# Speedy_V2.net
KiCad netlist of a schematic drawn in EAGLE
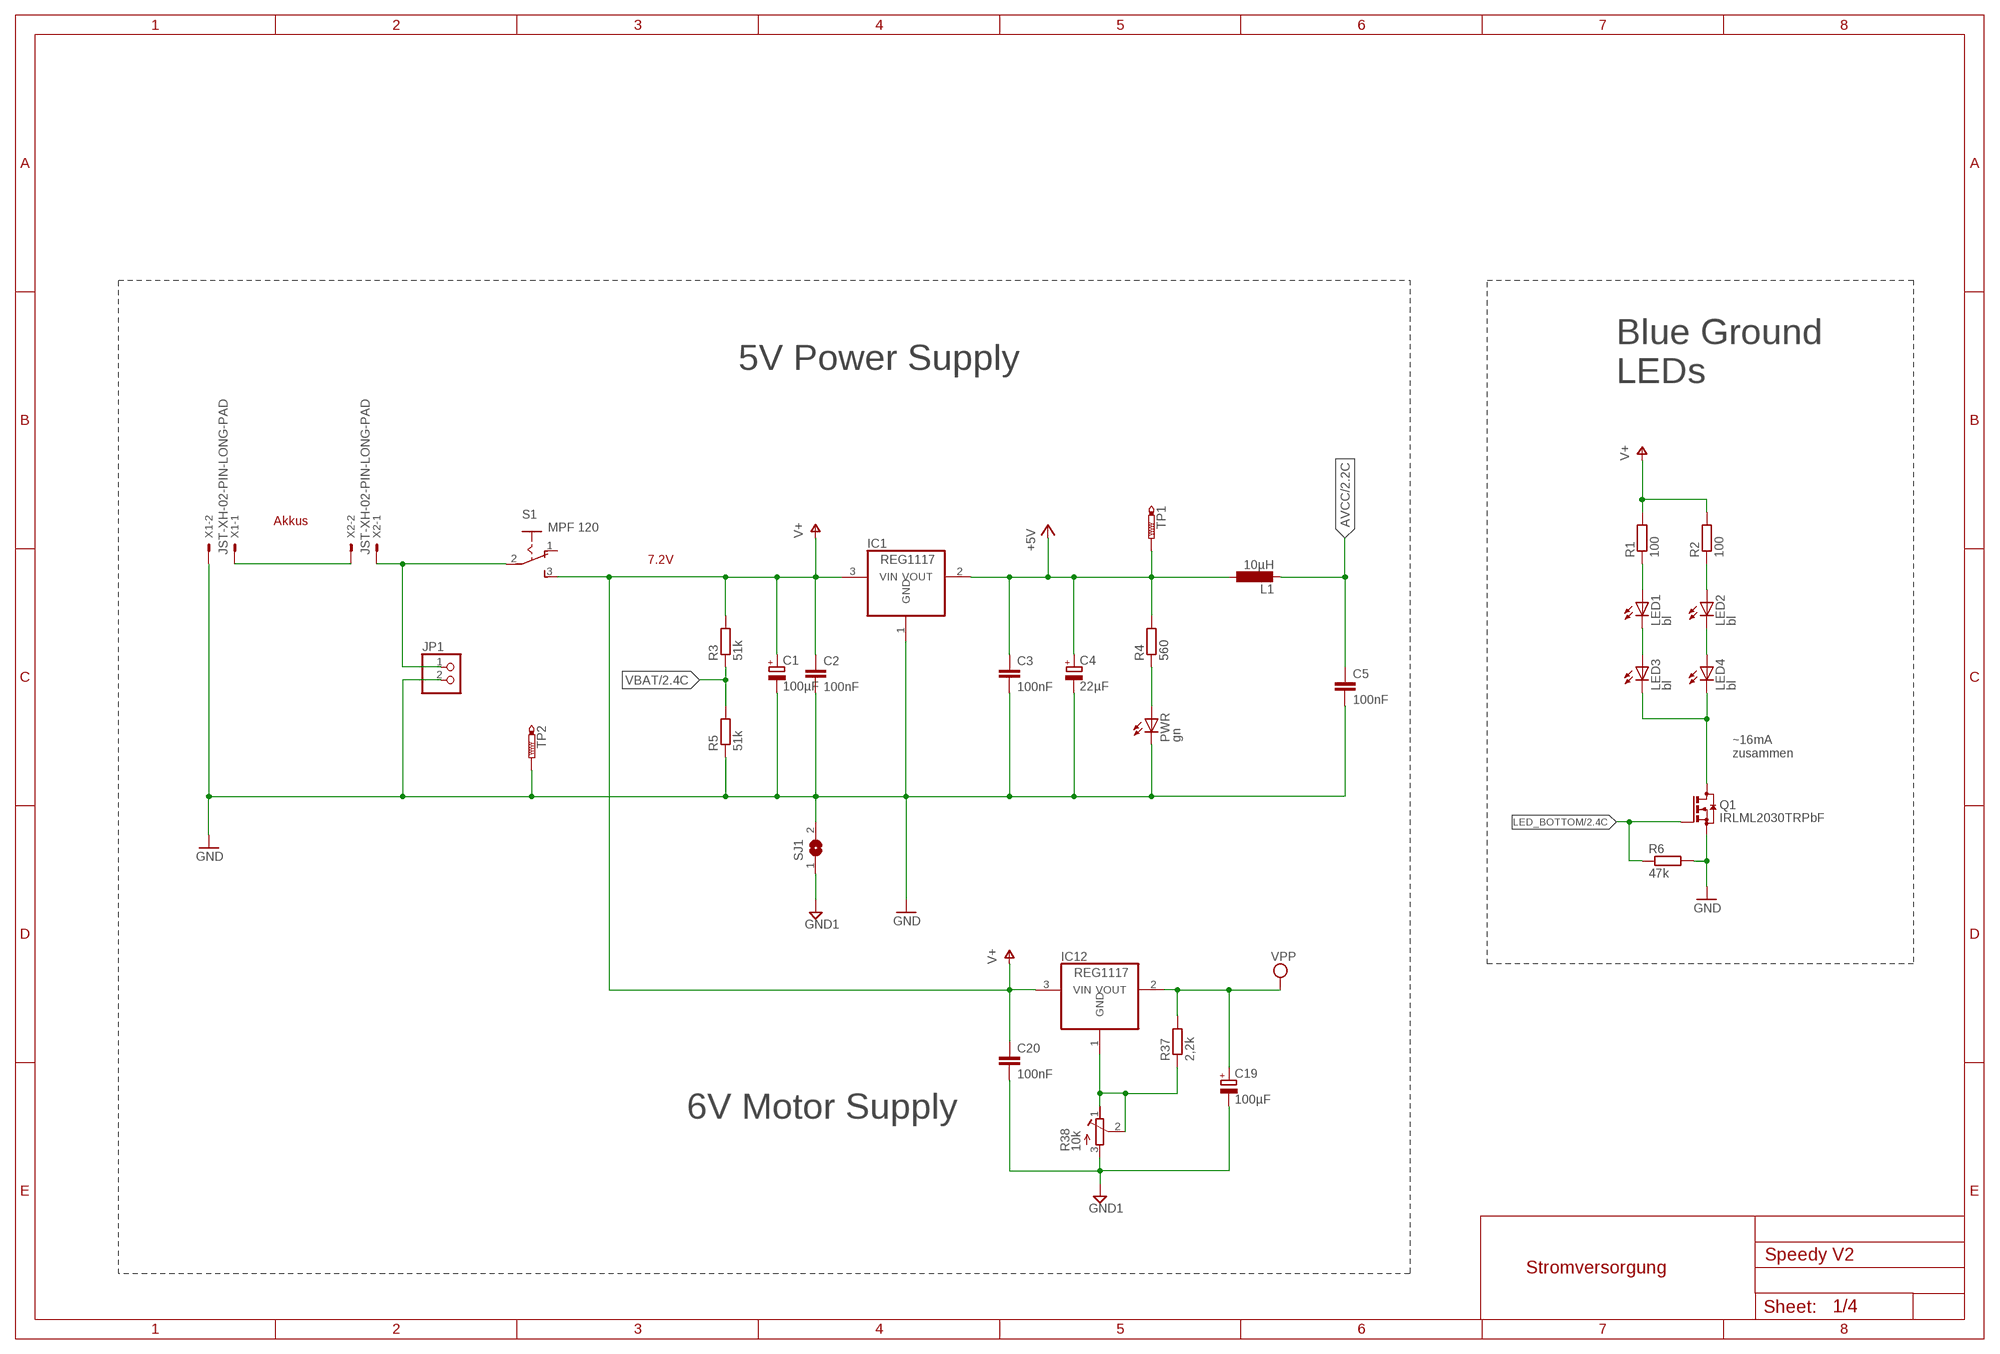
[diagram p0: schematic, sheet 1]
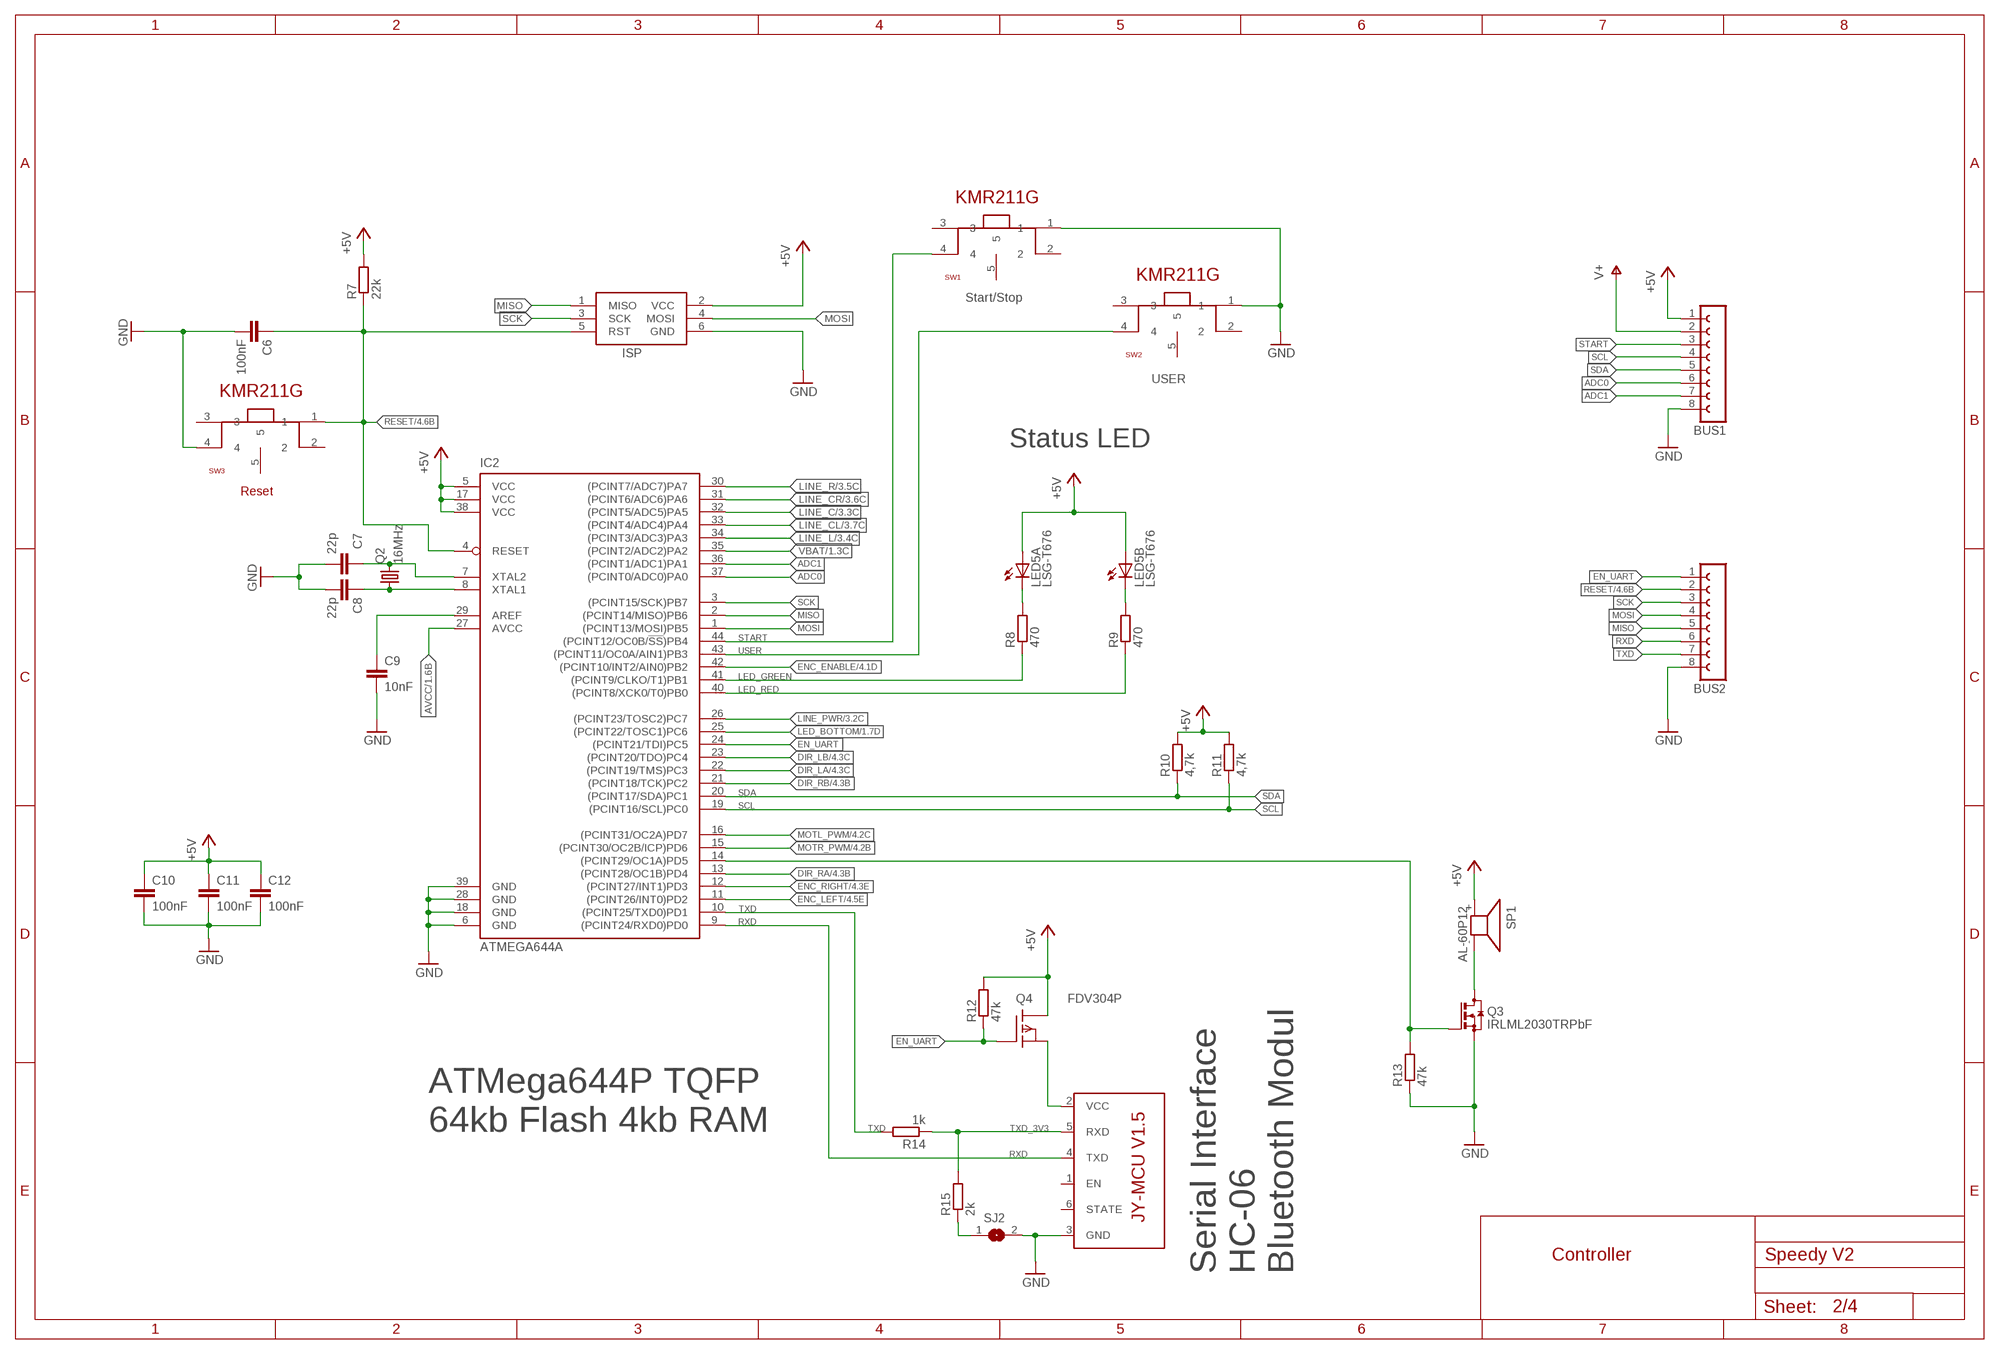
[diagram p1: schematic, sheet 2]
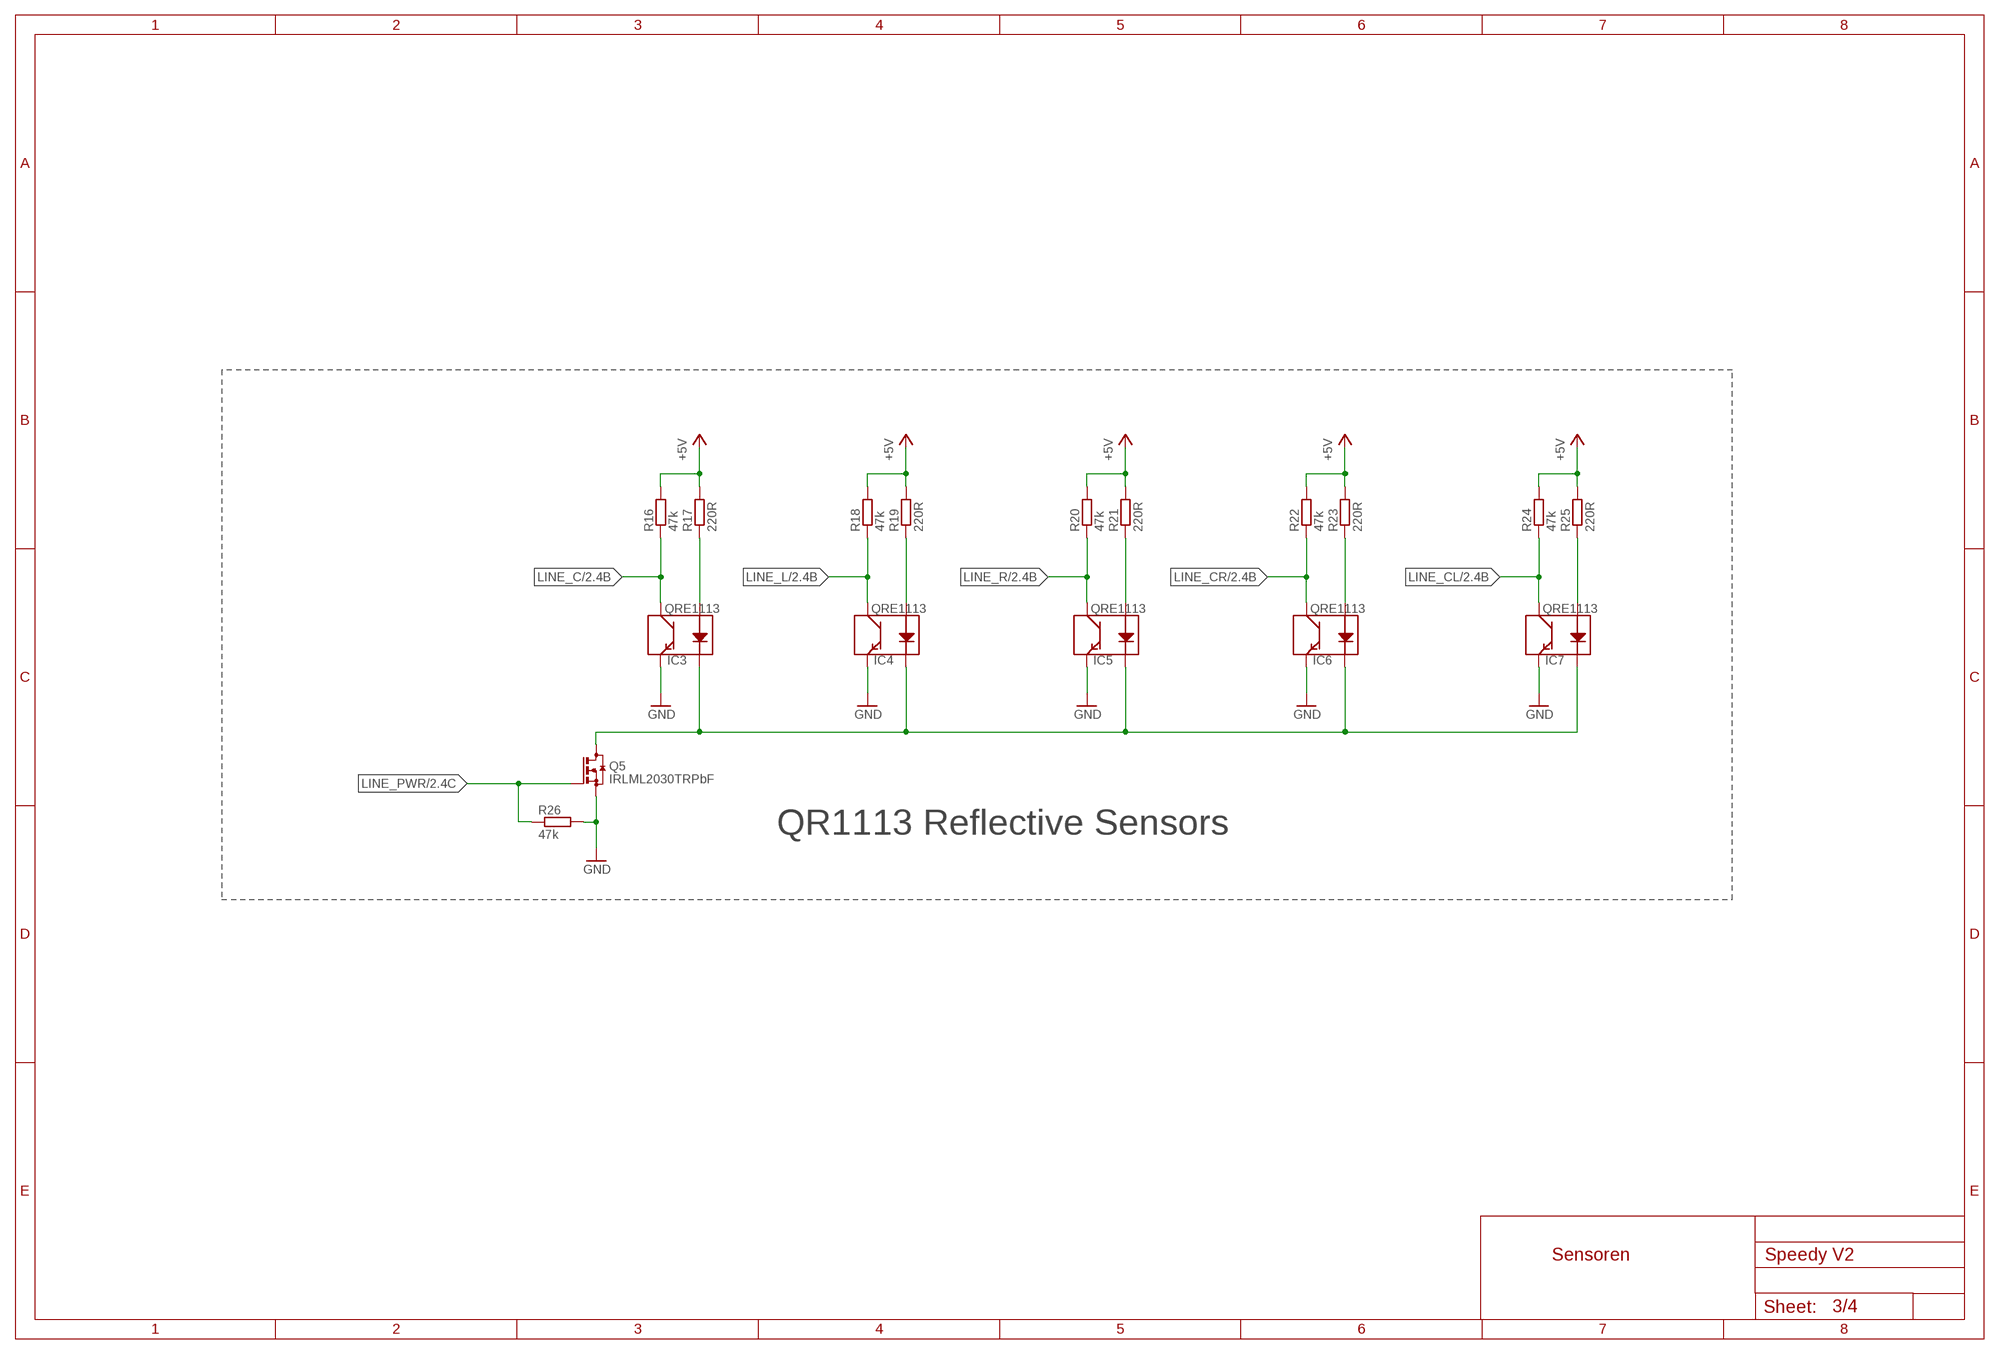
[diagram p2: schematic, sheet 3]
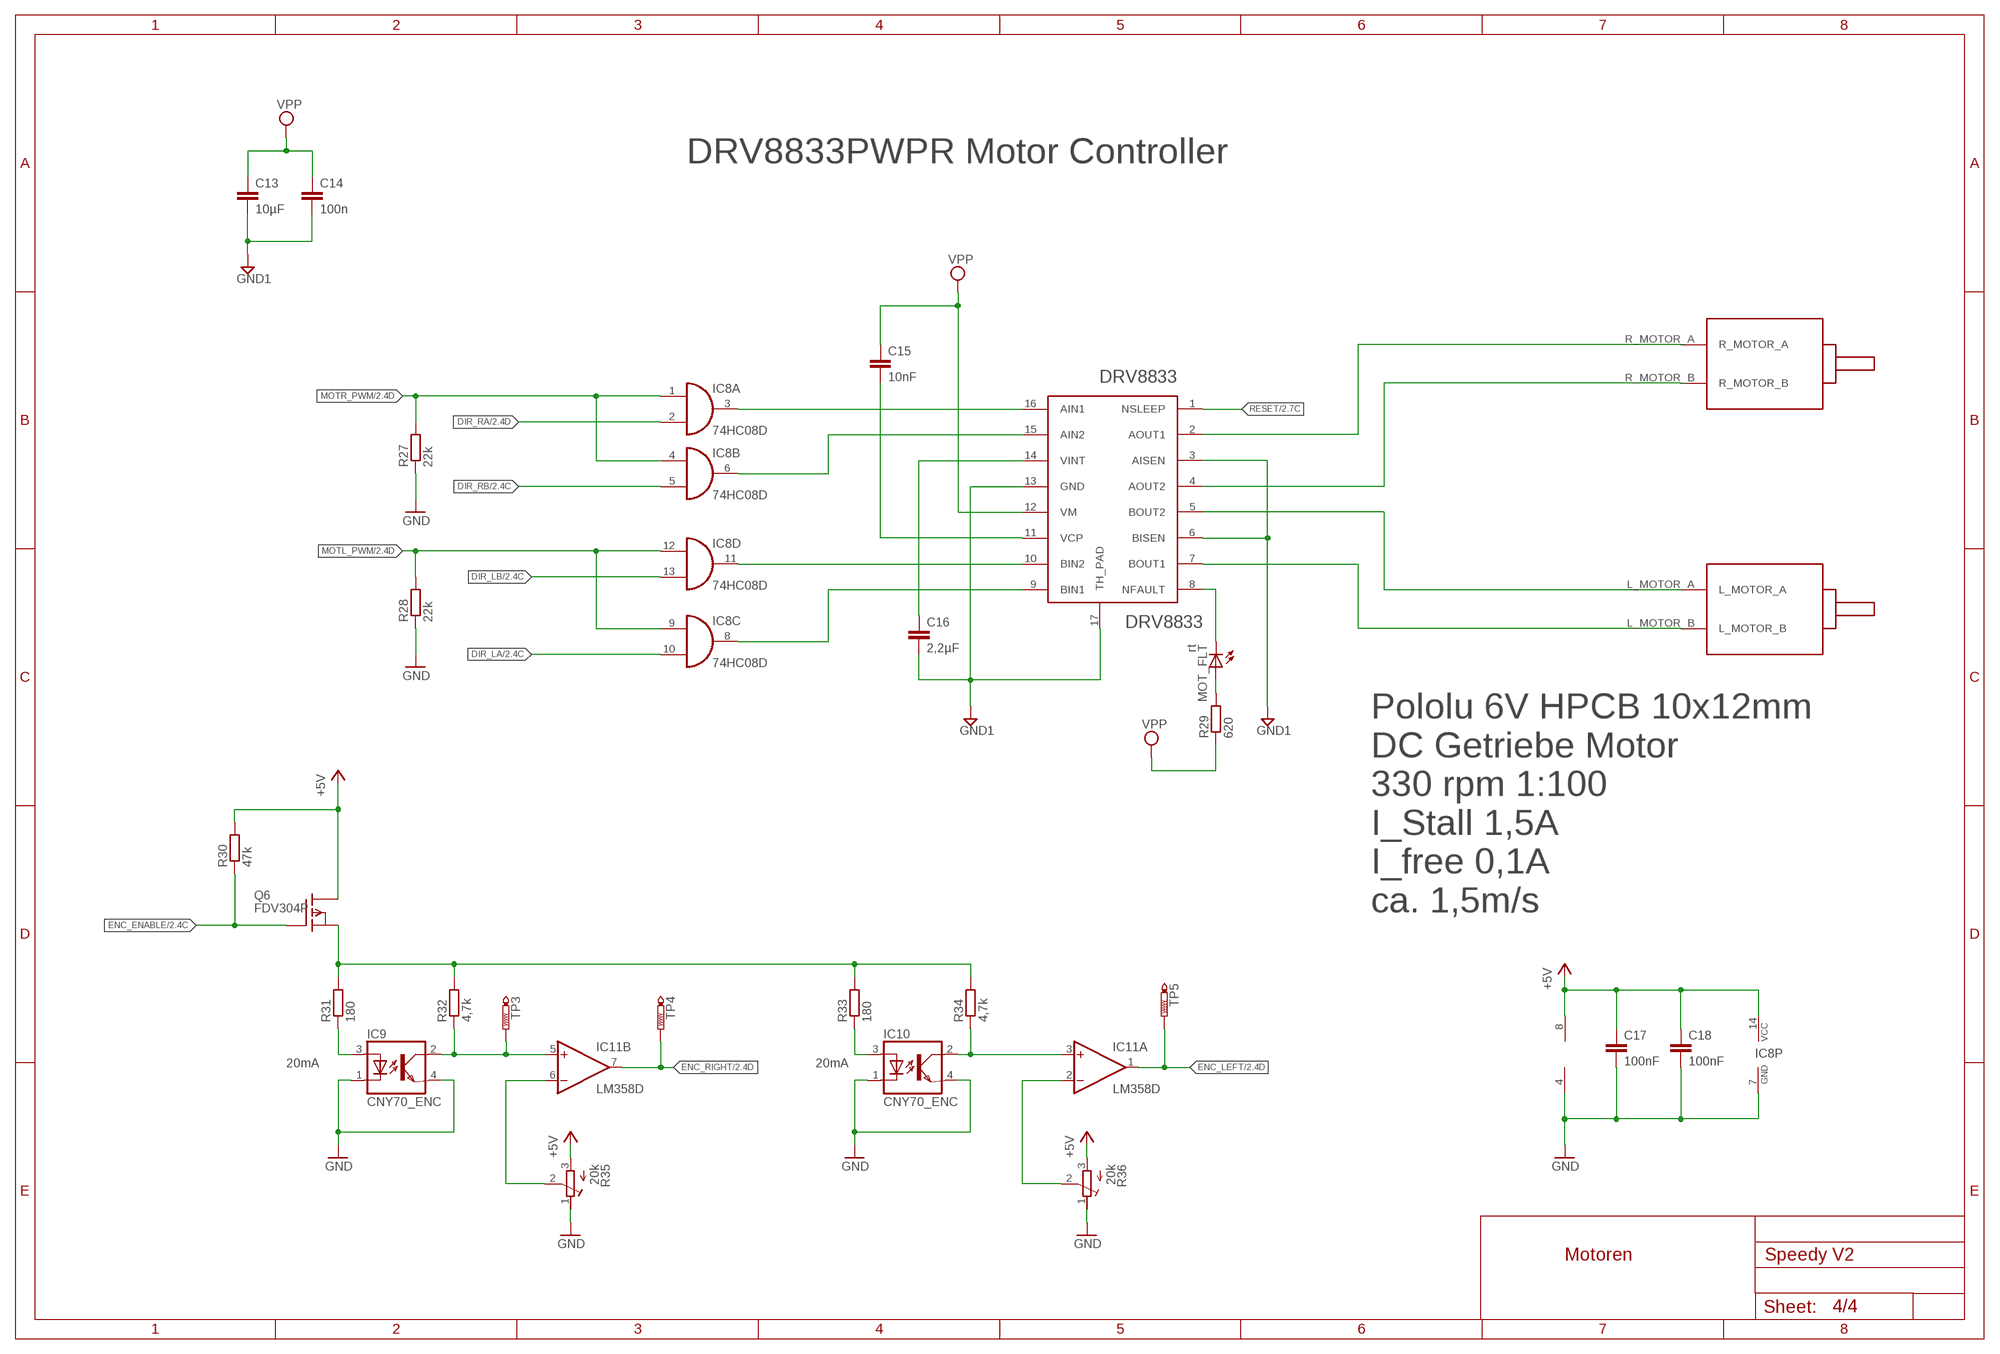
[diagram p3: schematic, sheet 4]

(export (version "E")
  (design (tool "Eeschema 10.0.6"))
  (components
    (comp (ref "IC3")
      (value "QRE1113")
      (footprint "eagle-import:QRE1113")
      (libsource (lib "eagle-import") (part "QRE1113"))
    )
    (comp (ref "IC4")
      (value "QRE1113")
      (footprint "eagle-import:QRE1113")
      (libsource (lib "eagle-import") (part "QRE1113"))
    )
    (comp (ref "IC5")
      (value "QRE1113")
      (footprint "eagle-import:QRE1113")
      (libsource (lib "eagle-import") (part "QRE1113"))
    )
    (comp (ref "IC6")
      (value "QRE1113")
      (footprint "eagle-import:QRE1113")
      (libsource (lib "eagle-import") (part "QRE1113"))
    )
    (comp (ref "IC7")
      (value "QRE1113")
      (footprint "eagle-import:QRE1113")
      (libsource (lib "eagle-import") (part "QRE1113"))
    )
    (comp (ref "Q5")
      (value "IRLML2030TRPbF")
      (footprint "eagle-import:SOT23")
      (libsource (lib "eagle-import") (part "BSS123"))
    )
    (comp (ref "R16")
      (value "47k")
      (footprint "eagle-import:R0805")
      (libsource (lib "eagle-import") (part "R-EU_R0805"))
    )
    (comp (ref "R17")
      (value "220R")
      (footprint "eagle-import:R0805")
      (libsource (lib "eagle-import") (part "R-EU_R0805"))
    )
    (comp (ref "R18")
      (value "47k")
      (footprint "eagle-import:R0805")
      (libsource (lib "eagle-import") (part "R-EU_R0805"))
    )
    (comp (ref "R19")
      (value "220R")
      (footprint "eagle-import:R0805")
      (libsource (lib "eagle-import") (part "R-EU_R0805"))
    )
    (comp (ref "R20")
      (value "47k")
      (footprint "eagle-import:R0805")
      (libsource (lib "eagle-import") (part "R-EU_R0805"))
    )
    (comp (ref "R21")
      (value "220R")
      (footprint "eagle-import:R0805")
      (libsource (lib "eagle-import") (part "R-EU_R0805"))
    )
    (comp (ref "R22")
      (value "47k")
      (footprint "eagle-import:R0805")
      (libsource (lib "eagle-import") (part "R-EU_R0805"))
    )
    (comp (ref "R23")
      (value "220R")
      (footprint "eagle-import:R0805")
      (libsource (lib "eagle-import") (part "R-EU_R0805"))
    )
    (comp (ref "R24")
      (value "47k")
      (footprint "eagle-import:R0805")
      (libsource (lib "eagle-import") (part "R-EU_R0805"))
    )
    (comp (ref "R25")
      (value "220R")
      (footprint "eagle-import:R0805")
      (libsource (lib "eagle-import") (part "R-EU_R0805"))
    )
    (comp (ref "R26")
      (value "47k")
      (footprint "eagle-import:R0805")
      (libsource (lib "eagle-import") (part "R-EU_R0805"))
    )
    (comp (ref "C13")
      (value "10µF")
      (footprint "eagle-import:C1206")
      (libsource (lib "eagle-import") (part "C-EUC1206"))
    )
    (comp (ref "C14")
      (value "100n")
      (footprint "eagle-import:C0805")
      (libsource (lib "eagle-import") (part "C-EUC0805"))
    )
    (comp (ref "C15")
      (value "10nF")
      (footprint "eagle-import:C0805")
      (libsource (lib "eagle-import") (part "C-EUC0805"))
    )
    (comp (ref "C16")
      (value "2,2µF")
      (footprint "eagle-import:C1206")
      (libsource (lib "eagle-import") (part "C-EUC1206"))
    )
    (comp (ref "C17")
      (value "100nF")
      (footprint "eagle-import:C0805")
      (libsource (lib "eagle-import") (part "C-EUC0805"))
    )
    (comp (ref "C18")
      (value "100nF")
      (footprint "eagle-import:C0805")
      (libsource (lib "eagle-import") (part "C-EUC0805"))
    )
    (comp (ref "IC8")
      (value "74HC08D")
      (footprint "eagle-import:SO14")
      (libsource (lib "eagle-import") (part "7408DHC"))
    )
    (comp (ref "IC9")
      (value "CNY70_ENC")
      (footprint "eagle-import:CNY70_ENC")
      (libsource (lib "eagle-import") (part "CNY70_ENC"))
    )
    (comp (ref "IC10")
      (value "CNY70_ENC")
      (footprint "eagle-import:CNY70_ENC")
      (libsource (lib "eagle-import") (part "CNY70_ENC"))
    )
    (comp (ref "IC11")
      (value "LM358D")
      (footprint "eagle-import:SO08")
      (libsource (lib "eagle-import") (part "LM358D"))
    )
    (comp (ref "MOT_FLT")
      (value "rt")
      (footprint "eagle-import:CHIP-LED0805")
      (libsource (lib "eagle-import") (part "LEDCHIP-LED0805"))
    )
    (comp (ref "Q6")
      (value "FDV304P")
      (footprint "eagle-import:SOT23")
      (libsource (lib "eagle-import") (part "FDV304P"))
    )
    (comp (ref "R27")
      (value "22k")
      (footprint "eagle-import:R0805")
      (libsource (lib "eagle-import") (part "R-EU_R0805"))
    )
    (comp (ref "R28")
      (value "22k")
      (footprint "eagle-import:R0805")
      (libsource (lib "eagle-import") (part "R-EU_R0805"))
    )
    (comp (ref "R29")
      (value "620")
      (footprint "eagle-import:R0805")
      (libsource (lib "eagle-import") (part "R-EU_R0805"))
    )
    (comp (ref "R30")
      (value "47k")
      (footprint "eagle-import:R0805")
      (libsource (lib "eagle-import") (part "R-EU_R0805"))
    )
    (comp (ref "R31")
      (value "180")
      (footprint "eagle-import:R0805")
      (libsource (lib "eagle-import") (part "R-EU_R0805"))
    )
    (comp (ref "R32")
      (value "4,7k")
      (footprint "eagle-import:R0805")
      (libsource (lib "eagle-import") (part "R-EU_R0805"))
    )
    (comp (ref "R33")
      (value "180")
      (footprint "eagle-import:R0805")
      (libsource (lib "eagle-import") (part "R-EU_R0805"))
    )
    (comp (ref "R34")
      (value "4,7k")
      (footprint "eagle-import:R0805")
      (libsource (lib "eagle-import") (part "R-EU_R0805"))
    )
    (comp (ref "R35")
      (value "20k")
      (footprint "eagle-import:RTRIM3314G")
      (libsource (lib "eagle-import") (part "R-TRIMM3314G"))
    )
    (comp (ref "R36")
      (value "20k")
      (footprint "eagle-import:RTRIM3314G")
      (libsource (lib "eagle-import") (part "R-TRIMM3314G"))
    )
    (comp (ref "TP3")
      (value "PTR1B1,27")
      (footprint "eagle-import:B1,27")
      (libsource (lib "eagle-import") (part "PTR1B1,27"))
    )
    (comp (ref "TP4")
      (value "PTR1B1,27")
      (footprint "eagle-import:B1,27")
      (libsource (lib "eagle-import") (part "PTR1B1,27"))
    )
    (comp (ref "TP5")
      (value "PTR1B1,27")
      (footprint "eagle-import:B1,27")
      (libsource (lib "eagle-import") (part "PTR1B1,27"))
    )
    (comp (ref "U2")
      (value "FUTURA_V1.0_MOTOR_MOUNT")
      (footprint "eagle-import:FUTURA_V1.0_MOTOT_MOUNT")
      (libsource (lib "eagle-import") (part "FUTURA_V1.0_MOTOR_MOUNT"))
    )
    (comp (ref "U3")
      (value "DRV8833")
      (footprint "eagle-import:SOP65P640X120-17N")
      (libsource (lib "eagle-import") (part "DRV8833"))
    )
    (comp (ref "C1")
      (value "100µF")
      (footprint "eagle-import:PANASONIC_D")
      (libsource (lib "eagle-import") (part "CPOL-EUD"))
    )
    (comp (ref "C2")
      (value "100nF")
      (footprint "eagle-import:C0805")
      (libsource (lib "eagle-import") (part "C-EUC0805"))
    )
    (comp (ref "C3")
      (value "100nF")
      (footprint "eagle-import:C0805")
      (libsource (lib "eagle-import") (part "C-EUC0805"))
    )
    (comp (ref "C4")
      (value "22µF")
      (footprint "eagle-import:PANASONIC_B")
      (libsource (lib "eagle-import") (part "CPOL-EUB"))
    )
    (comp (ref "C5")
      (value "100nF")
      (footprint "eagle-import:C0805")
      (libsource (lib "eagle-import") (part "C-EUC0805"))
    )
    (comp (ref "C19")
      (value "100µF")
      (footprint "eagle-import:PANASONIC_D")
      (libsource (lib "eagle-import") (part "CPOL-EUD"))
    )
    (comp (ref "C20")
      (value "100nF")
      (footprint "eagle-import:C0805")
      (libsource (lib "eagle-import") (part "C-EUC0805"))
    )
    (comp (ref "IC1")
      (value "REG1117")
      (footprint "eagle-import:SOT223")
      (libsource (lib "eagle-import") (part "REG1117"))
    )
    (comp (ref "IC12")
      (value "REG1117")
      (footprint "eagle-import:SOT223")
      (libsource (lib "eagle-import") (part "REG1117"))
    )
    (comp (ref "JP1")
      (value "PINHD-1X2")
      (footprint "eagle-import:1X02")
      (libsource (lib "eagle-import") (part "PINHD-1X2"))
    )
    (comp (ref "L1")
      (value "10µH")
      (footprint "eagle-import:C1210K")
      (libsource (lib "eagle-import") (part "L-1210"))
    )
    (comp (ref "LED1")
      (value "bl")
      (footprint "eagle-import:CHIPLED_0805")
      (libsource (lib "eagle-import") (part "LEDCHIPLED_0805"))
    )
    (comp (ref "LED2")
      (value "bl")
      (footprint "eagle-import:CHIPLED_0805")
      (libsource (lib "eagle-import") (part "LEDCHIPLED_0805"))
    )
    (comp (ref "LED3")
      (value "bl")
      (footprint "eagle-import:CHIPLED_0805")
      (libsource (lib "eagle-import") (part "LEDCHIPLED_0805"))
    )
    (comp (ref "LED4")
      (value "bl")
      (footprint "eagle-import:CHIPLED_0805")
      (libsource (lib "eagle-import") (part "LEDCHIPLED_0805"))
    )
    (comp (ref "PWR")
      (value "gn")
      (footprint "eagle-import:CHIPLED_0805")
      (libsource (lib "eagle-import") (part "LEDCHIPLED_0805"))
    )
    (comp (ref "Q1")
      (value "IRLML2030TRPbF")
      (footprint "eagle-import:SOT23")
      (libsource (lib "eagle-import") (part "BSS123"))
    )
    (comp (ref "R1")
      (value "100")
      (footprint "eagle-import:R0805")
      (libsource (lib "eagle-import") (part "R-EU_R0805"))
    )
    (comp (ref "R2")
      (value "100")
      (footprint "eagle-import:R0805")
      (libsource (lib "eagle-import") (part "R-EU_R0805"))
    )
    (comp (ref "R3")
      (value "51k")
      (footprint "eagle-import:R0805")
      (libsource (lib "eagle-import") (part "R-EU_R0805"))
    )
    (comp (ref "R4")
      (value "560")
      (footprint "eagle-import:R0805")
      (libsource (lib "eagle-import") (part "R-EU_R0805"))
    )
    (comp (ref "R5")
      (value "51k")
      (footprint "eagle-import:R0805")
      (libsource (lib "eagle-import") (part "R-EU_R0805"))
    )
    (comp (ref "R6")
      (value "47k")
      (footprint "eagle-import:R0805")
      (libsource (lib "eagle-import") (part "R-EU_R0805"))
    )
    (comp (ref "R37")
      (value "2,2k")
      (footprint "eagle-import:R0805")
      (libsource (lib "eagle-import") (part "R-EU_R0805"))
    )
    (comp (ref "R38")
      (value "10k")
      (footprint "eagle-import:RTRIM3314G")
      (libsource (lib "eagle-import") (part "R-TRIMM3314G"))
    )
    (comp (ref "S1")
      (value "MPF 120")
      (footprint "eagle-import:255SB")
      (libsource (lib "eagle-import") (part "255SB"))
    )
    (comp (ref "SJ1") (value "SJ") (footprint "eagle-import:SJ") (libsource (lib "eagle-import") (part "SJ")))
    (comp (ref "TP1")
      (value "PTR1B1,27")
      (footprint "eagle-import:B1,27")
      (libsource (lib "eagle-import") (part "PTR1B1,27"))
    )
    (comp (ref "TP2")
      (value "PTR1PAD1-13")
      (footprint "eagle-import:P1-13")
      (libsource (lib "eagle-import") (part "PTR1PAD1-13"))
    )
    (comp (ref "X1")
      (value "JST-XH-02-PIN-LONG-PAD")
      (footprint "eagle-import:JST-XH-02-PACKAGE-LONG-PAD")
      (libsource (lib "eagle-import") (part "JST-XH-02-PIN-LONG-PAD"))
    )
    (comp (ref "X2")
      (value "JST-XH-02-PIN-LONG-PAD")
      (footprint "eagle-import:JST-XH-02-PACKAGE-LONG-PAD")
      (libsource (lib "eagle-import") (part "JST-XH-02-PIN-LONG-PAD"))
    )
    (comp (ref "BUS1")
      (value "FE08-1")
      (footprint "eagle-import:FE08")
      (libsource (lib "eagle-import") (part "FE08-1"))
    )
    (comp (ref "BUS2")
      (value "FE08-1")
      (footprint "eagle-import:FE08")
      (libsource (lib "eagle-import") (part "FE08-1"))
    )
    (comp (ref "C6")
      (value "100nF")
      (footprint "eagle-import:C0805")
      (libsource (lib "eagle-import") (part "C-EUC0805"))
    )
    (comp (ref "C7")
      (value "22p")
      (footprint "eagle-import:C0603")
      (libsource (lib "eagle-import") (part "C-EUC0603"))
    )
    (comp (ref "C8")
      (value "22p")
      (footprint "eagle-import:C0603")
      (libsource (lib "eagle-import") (part "C-EUC0603"))
    )
    (comp (ref "C9")
      (value "10nF")
      (footprint "eagle-import:C0603")
      (libsource (lib "eagle-import") (part "C-EUC0603"))
    )
    (comp (ref "C10")
      (value "100nF")
      (footprint "eagle-import:C0603")
      (libsource (lib "eagle-import") (part "C-EUC0603"))
    )
    (comp (ref "C11")
      (value "100nF")
      (footprint "eagle-import:C0603")
      (libsource (lib "eagle-import") (part "C-EUC0603"))
    )
    (comp (ref "C12")
      (value "100nF")
      (footprint "eagle-import:C0603")
      (libsource (lib "eagle-import") (part "C-EUC0603"))
    )
    (comp (ref "IC2")
      (value "ATMEGA644A")
      (footprint "eagle-import:TQFP44")
      (fields (field (name "MPN") "ATMEGA644PV-10AU"))
      (libsource (lib "eagle-import") (part "ATMEGA644A"))
    )
    (comp (ref "ISP")
      (value "AVRISP-6")
      (footprint "eagle-import:AVRISP")
      (libsource (lib "eagle-import") (part "AVRISP-6"))
    )
    (comp (ref "LED5")
      (value "LSG-T676")
      (footprint "eagle-import:P-LCC4-0")
      (libsource (lib "eagle-import") (part "LSG-T676"))
    )
    (comp (ref "Q2")
      (value "16MHz")
      (footprint "eagle-import:7X5MMQUARZ")
      (libsource (lib "eagle-import") (part "7X5MMMQ"))
    )
    (comp (ref "Q3")
      (value "IRLML2030TRPbF")
      (footprint "eagle-import:SOT23")
      (libsource (lib "eagle-import") (part "BSS123"))
    )
    (comp (ref "Q4")
      (value "FDV304P")
      (footprint "eagle-import:SOT23")
      (libsource (lib "eagle-import") (part "FDV304P"))
    )
    (comp (ref "R7")
      (value "22k")
      (footprint "eagle-import:R0805")
      (libsource (lib "eagle-import") (part "R-EU_R0805"))
    )
    (comp (ref "R8")
      (value "470")
      (footprint "eagle-import:R0805")
      (libsource (lib "eagle-import") (part "R-EU_R0805"))
    )
    (comp (ref "R9")
      (value "470")
      (footprint "eagle-import:R0805")
      (libsource (lib "eagle-import") (part "R-EU_R0805"))
    )
    (comp (ref "R10")
      (value "4,7k")
      (footprint "eagle-import:R0805")
      (libsource (lib "eagle-import") (part "R-EU_R0805"))
    )
    (comp (ref "R11")
      (value "4,7k")
      (footprint "eagle-import:R0805")
      (libsource (lib "eagle-import") (part "R-EU_R0805"))
    )
    (comp (ref "R12")
      (value "47k")
      (footprint "eagle-import:R0805")
      (libsource (lib "eagle-import") (part "R-EU_R0805"))
    )
    (comp (ref "R13")
      (value "47k")
      (footprint "eagle-import:R0805")
      (libsource (lib "eagle-import") (part "R-EU_R0805"))
    )
    (comp (ref "R14")
      (value "1k")
      (footprint "eagle-import:R0805")
      (libsource (lib "eagle-import") (part "R-EU_R0805"))
    )
    (comp (ref "R15")
      (value "2k")
      (footprint "eagle-import:R0805")
      (libsource (lib "eagle-import") (part "R-EU_R0805"))
    )
    (comp (ref "SJ2") (value "SJ") (footprint "eagle-import:SJ") (libsource (lib "eagle-import") (part "SJ")))
    (comp (ref "SP1")
      (value "AL-60P12")
      (footprint "eagle-import:KSS1201")
      (libsource (lib "eagle-import") (part "KSS1201"))
    )
    (comp (ref "SW1")
      (value "KMR211G_SWITCH")
      (footprint "eagle-import:KMR211G_SWITCH")
      (libsource (lib "eagle-import") (part "KMR211G_SWITCH"))
    )
    (comp (ref "SW2")
      (value "KMR211G_SWITCH")
      (footprint "eagle-import:KMR211G_SWITCH")
      (libsource (lib "eagle-import") (part "KMR211G_SWITCH"))
    )
    (comp (ref "SW3")
      (value "KMR211G_SWITCH")
      (footprint "eagle-import:KMR211G_SWITCH")
      (libsource (lib "eagle-import") (part "KMR211G_SWITCH"))
    )
    (comp (ref "U1")
      (value "BT_BOARD")
      (footprint "eagle-import:BT_BOARD")
      (libsource (lib "eagle-import") (part "BT_BOARD"))
    )
  )
  (nets
    (net (code "1") (name "+5V") (class "Default")
      (node (ref "BUS1") (pin "1") (pinfunction "1_1") (pintype "passive"))
      (node (ref "C10") (pin "1") (pinfunction "1_1") (pintype "passive"))
      (node (ref "C11") (pin "1") (pinfunction "1_1") (pintype "passive"))
      (node (ref "C12") (pin "1") (pinfunction "1_1") (pintype "passive"))
      (node (ref "C17") (pin "1") (pinfunction "1_1") (pintype "passive"))
      (node (ref "C18") (pin "1") (pinfunction "1_1") (pintype "passive"))
      (node (ref "C3") (pin "1") (pinfunction "1_1") (pintype "passive"))
      (node (ref "C4") (pin "+") (pinfunction "+_+") (pintype "passive"))
      (node (ref "IC1") (pin "2") (pinfunction "VOUT_2") (pintype "output"))
      (node (ref "IC11") (pin "8") (pinfunction "V+_8") (pintype "power_in"))
      (node (ref "IC2") (pin "17") (pinfunction "VCC_17") (pintype "power_in"))
      (node (ref "IC2") (pin "38") (pinfunction "VCC_38") (pintype "power_in"))
      (node (ref "IC2") (pin "5") (pinfunction "VCC_5") (pintype "power_in"))
      (node (ref "IC8") (pin "14") (pinfunction "VCC_14") (pintype "power_in"))
      (node (ref "ISP") (pin "2") (pinfunction "VCC_2") (pintype "power_in"))
      (node (ref "L1") (pin "1") (pinfunction "1_1") (pintype "passive"))
      (node (ref "LED5") (pin "2") (pinfunction "A_2") (pintype "passive"))
      (node (ref "LED5") (pin "4") (pinfunction "A_4") (pintype "passive"))
      (node (ref "Q4") (pin "D") (pinfunction "D_D") (pintype "passive"))
      (node (ref "Q6") (pin "D") (pinfunction "D_D") (pintype "passive"))
      (node (ref "R10") (pin "2") (pinfunction "2_2") (pintype "passive"))
      (node (ref "R11") (pin "2") (pinfunction "2_2") (pintype "passive"))
      (node (ref "R12") (pin "2") (pinfunction "2_2") (pintype "passive"))
      (node (ref "R16") (pin "2") (pinfunction "2_2") (pintype "passive"))
      (node (ref "R17") (pin "2") (pinfunction "2_2") (pintype "passive"))
      (node (ref "R18") (pin "2") (pinfunction "2_2") (pintype "passive"))
      (node (ref "R19") (pin "2") (pinfunction "2_2") (pintype "passive"))
      (node (ref "R20") (pin "2") (pinfunction "2_2") (pintype "passive"))
      (node (ref "R21") (pin "2") (pinfunction "2_2") (pintype "passive"))
      (node (ref "R22") (pin "2") (pinfunction "2_2") (pintype "passive"))
      (node (ref "R23") (pin "2") (pinfunction "2_2") (pintype "passive"))
      (node (ref "R24") (pin "2") (pinfunction "2_2") (pintype "passive"))
      (node (ref "R25") (pin "2") (pinfunction "2_2") (pintype "passive"))
      (node (ref "R30") (pin "2") (pinfunction "2_2") (pintype "passive"))
      (node (ref "R35") (pin "3") (pinfunction "A_3") (pintype "passive"))
      (node (ref "R36") (pin "3") (pinfunction "A_3") (pintype "passive"))
      (node (ref "R4") (pin "2") (pinfunction "2_2") (pintype "passive"))
      (node (ref "R7") (pin "2") (pinfunction "2_2") (pintype "passive"))
      (node (ref "SP1") (pin "+") (pinfunction "1_+") (pintype "passive"))
      (node (ref "TP1") (pin "TP") (pinfunction "TP_TP") (pintype "input"))
    )
    (net (code "2") (name "ADC0") (class "Default")
      (node (ref "BUS1") (pin "6") (pinfunction "6_6") (pintype "passive"))
      (node (ref "IC2") (pin "37") (pinfunction "(PCINT0/ADC0)PA0_37") (pintype "bidirectional"))
    )
    (net (code "3") (name "ADC1") (class "Default")
      (node (ref "BUS1") (pin "7") (pinfunction "7_7") (pintype "passive"))
      (node (ref "IC2") (pin "36") (pinfunction "(PCINT1/ADC1)PA1_36") (pintype "bidirectional"))
    )
    (net (code "4") (name "AVCC") (class "Default")
      (node (ref "C5") (pin "1") (pinfunction "1_1") (pintype "passive"))
      (node (ref "IC2") (pin "27") (pinfunction "AVCC_27") (pintype "power_in"))
      (node (ref "L1") (pin "2") (pinfunction "2_2") (pintype "passive"))
    )
    (net (code "5") (name "DIR_LA") (class "Default")
      (node (ref "IC2") (pin "22") (pinfunction "(PCINT19/TMS)PC3_22") (pintype "output"))
      (node (ref "IC8") (pin "10") (pinfunction "I1_10") (pintype "input"))
    )
    (net (code "6") (name "DIR_LB") (class "Default")
      (node (ref "IC2") (pin "23") (pinfunction "(PCINT20/TDO)PC4_23") (pintype "output"))
      (node (ref "IC8") (pin "13") (pinfunction "I1_13") (pintype "input"))
    )
    (net (code "7") (name "DIR_RA") (class "Default")
      (node (ref "IC2") (pin "13") (pinfunction "(PCINT28/OC1B)PD4_13") (pintype "bidirectional"))
      (node (ref "IC8") (pin "2") (pinfunction "I1_2") (pintype "input"))
    )
    (net (code "8") (name "DIR_RB") (class "Default")
      (node (ref "IC2") (pin "21") (pinfunction "(PCINT18/TCK)PC2_21") (pintype "output"))
      (node (ref "IC8") (pin "5") (pinfunction "I1_5") (pintype "input"))
    )
    (net (code "9") (name "ENC_ENABLE") (class "Default")
      (node (ref "IC2") (pin "42") (pinfunction "(PCINT10/INT2/AIN0)PB2_42") (pintype "bidirectional"))
      (node (ref "Q6") (pin "G") (pinfunction "G_G") (pintype "passive"))
      (node (ref "R30") (pin "1") (pinfunction "1_1") (pintype "passive"))
    )
    (net (code "10") (name "ENC_LEFT") (class "Default")
      (node (ref "IC11") (pin "1") (pinfunction "OUT_1") (pintype "output"))
      (node (ref "IC2") (pin "11") (pinfunction "(PCINT26/INT0)PD2_11") (pintype "bidirectional"))
      (node (ref "TP5") (pin "TP") (pinfunction "TP_TP") (pintype "input"))
    )
    (net (code "11") (name "ENC_RIGHT") (class "Default")
      (node (ref "IC11") (pin "7") (pinfunction "OUT_7") (pintype "output"))
      (node (ref "IC2") (pin "12") (pinfunction "(PCINT27/INT1)PD3_12") (pintype "bidirectional"))
      (node (ref "TP4") (pin "TP") (pinfunction "TP_TP") (pintype "input"))
    )
    (net (code "12") (name "EN_UART") (class "Default")
      (node (ref "BUS2") (pin "1") (pinfunction "1_1") (pintype "passive"))
      (node (ref "IC2") (pin "24") (pinfunction "(PCINT21/TDI)PC5_24") (pintype "output"))
      (node (ref "Q4") (pin "G") (pinfunction "G_G") (pintype "passive"))
      (node (ref "R12") (pin "1") (pinfunction "1_1") (pintype "passive"))
    )
    (net (code "13") (name "GND") (class "Default")
      (node (ref "BUS1") (pin "8") (pinfunction "8_8") (pintype "passive"))
      (node (ref "BUS2") (pin "8") (pinfunction "8_8") (pintype "passive"))
      (node (ref "C1") (pin "-") (pinfunction "-_-") (pintype "passive"))
      (node (ref "C10") (pin "2") (pinfunction "2_2") (pintype "passive"))
      (node (ref "C11") (pin "2") (pinfunction "2_2") (pintype "passive"))
      (node (ref "C12") (pin "2") (pinfunction "2_2") (pintype "passive"))
      (node (ref "C17") (pin "2") (pinfunction "2_2") (pintype "passive"))
      (node (ref "C18") (pin "2") (pinfunction "2_2") (pintype "passive"))
      (node (ref "C2") (pin "2") (pinfunction "2_2") (pintype "passive"))
      (node (ref "C3") (pin "2") (pinfunction "2_2") (pintype "passive"))
      (node (ref "C4") (pin "-") (pinfunction "-_-") (pintype "passive"))
      (node (ref "C5") (pin "2") (pinfunction "2_2") (pintype "passive"))
      (node (ref "C6") (pin "2") (pinfunction "2_2") (pintype "passive"))
      (node (ref "C7") (pin "2") (pinfunction "2_2") (pintype "passive"))
      (node (ref "C8") (pin "2") (pinfunction "2_2") (pintype "passive"))
      (node (ref "C9") (pin "2") (pinfunction "2_2") (pintype "passive"))
      (node (ref "IC1") (pin "1") (pinfunction "GND_1") (pintype "power_in"))
      (node (ref "IC10") (pin "1") (pinfunction "CATH._1") (pintype "passive"))
      (node (ref "IC10") (pin "4") (pinfunction "E_4") (pintype "passive"))
      (node (ref "IC11") (pin "4") (pinfunction "V-_4") (pintype "power_in"))
      (node (ref "IC2") (pin "18") (pinfunction "GND_18") (pintype "power_in"))
      (node (ref "IC2") (pin "28") (pinfunction "GND_28") (pintype "power_in"))
      (node (ref "IC2") (pin "39") (pinfunction "GND_39") (pintype "power_in"))
      (node (ref "IC2") (pin "6") (pinfunction "GND_6") (pintype "power_in"))
      (node (ref "IC3") (pin "4") (pinfunction "E_4") (pintype "bidirectional"))
      (node (ref "IC4") (pin "4") (pinfunction "E_4") (pintype "bidirectional"))
      (node (ref "IC5") (pin "4") (pinfunction "E_4") (pintype "bidirectional"))
      (node (ref "IC6") (pin "4") (pinfunction "E_4") (pintype "bidirectional"))
      (node (ref "IC7") (pin "4") (pinfunction "E_4") (pintype "bidirectional"))
      (node (ref "IC8") (pin "7") (pinfunction "GND_7") (pintype "power_in"))
      (node (ref "IC9") (pin "1") (pinfunction "CATH._1") (pintype "passive"))
      (node (ref "IC9") (pin "4") (pinfunction "E_4") (pintype "passive"))
      (node (ref "ISP") (pin "6") (pinfunction "GND_6") (pintype "power_in"))
      (node (ref "JP1") (pin "2") (pinfunction "2_2") (pintype "passive"))
      (node (ref "PWR") (pin "C") (pinfunction "C_C") (pintype "passive"))
      (node (ref "Q1") (pin "2") (pinfunction "S_2") (pintype "passive"))
      (node (ref "Q3") (pin "2") (pinfunction "S_2") (pintype "passive"))
      (node (ref "Q5") (pin "2") (pinfunction "S_2") (pintype "passive"))
      (node (ref "R13") (pin "1") (pinfunction "1_1") (pintype "passive"))
      (node (ref "R26") (pin "2") (pinfunction "2_2") (pintype "passive"))
      (node (ref "R27") (pin "1") (pinfunction "1_1") (pintype "passive"))
      (node (ref "R28") (pin "1") (pinfunction "1_1") (pintype "passive"))
      (node (ref "R35") (pin "1") (pinfunction "E_1") (pintype "passive"))
      (node (ref "R36") (pin "1") (pinfunction "E_1") (pintype "passive"))
      (node (ref "R5") (pin "1") (pinfunction "1_1") (pintype "passive"))
      (node (ref "R6") (pin "2") (pinfunction "2_2") (pintype "passive"))
      (node (ref "SJ1") (pin "2") (pinfunction "2_2") (pintype "passive"))
      (node (ref "SJ2") (pin "2") (pinfunction "2_2") (pintype "passive"))
      (node (ref "SW1") (pin "1") (pinfunction "1_1") (pintype "bidirectional"))
      (node (ref "SW2") (pin "1") (pinfunction "1_1") (pintype "bidirectional"))
      (node (ref "SW3") (pin "4") (pinfunction "4_4") (pintype "bidirectional"))
      (node (ref "TP2") (pin "TP") (pinfunction "TP_TP") (pintype "input"))
      (node (ref "U1") (pin "3") (pinfunction "GND_3") (pintype "bidirectional"))
      (node (ref "X1") (pin "2") (pinfunction "S_2") (pintype "passive"))
    )
    (net (code "14") (name "GND1") (class "Default")
      (node (ref "C13") (pin "2") (pinfunction "2_2") (pintype "passive"))
      (node (ref "C14") (pin "2") (pinfunction "2_2") (pintype "passive"))
      (node (ref "C16") (pin "2") (pinfunction "2_2") (pintype "passive"))
      (node (ref "C19") (pin "-") (pinfunction "-_-") (pintype "passive"))
      (node (ref "C20") (pin "2") (pinfunction "2_2") (pintype "passive"))
      (node (ref "R38") (pin "3") (pinfunction "A_3") (pintype "passive"))
      (node (ref "SJ1") (pin "1") (pinfunction "1_1") (pintype "passive"))
      (node (ref "U3") (pin "13") (pinfunction "GND_13") (pintype "bidirectional"))
      (node (ref "U3") (pin "17") (pinfunction "TH_PAD_17") (pintype "bidirectional"))
      (node (ref "U3") (pin "3") (pinfunction "AISEN_3") (pintype "bidirectional"))
      (node (ref "U3") (pin "6") (pinfunction "BISEN_6") (pintype "bidirectional"))
    )
    (net (code "15") (name "LED_BOTTOM") (class "Default")
      (node (ref "IC2") (pin "25") (pinfunction "(PCINT22/TOSC1)PC6_25") (pintype "output"))
      (node (ref "Q1") (pin "1") (pinfunction "G_1") (pintype "passive"))
      (node (ref "R6") (pin "1") (pinfunction "1_1") (pintype "passive"))
    )
    (net (code "16") (name "LED_GREEN") (class "Default")
      (node (ref "IC2") (pin "41") (pinfunction "(PCINT9/CLKO/T1)PB1_41") (pintype "bidirectional"))
      (node (ref "R8") (pin "1") (pinfunction "1_1") (pintype "passive"))
    )
    (net (code "17") (name "LED_RED") (class "Default")
      (node (ref "IC2") (pin "40") (pinfunction "(PCINT8/XCK0/T0)PB0_40") (pintype "bidirectional"))
      (node (ref "R9") (pin "1") (pinfunction "1_1") (pintype "passive"))
    )
    (net (code "18") (name "LINE_C") (class "Default")
      (node (ref "IC2") (pin "32") (pinfunction "(PCINT5/ADC5)PA5_32") (pintype "bidirectional"))
      (node (ref "IC3") (pin "3") (pinfunction "C_3") (pintype "bidirectional"))
      (node (ref "R16") (pin "1") (pinfunction "1_1") (pintype "passive"))
    )
    (net (code "19") (name "LINE_CL") (class "Default")
      (node (ref "IC2") (pin "33") (pinfunction "(PCINT4/ADC4)PA4_33") (pintype "bidirectional"))
      (node (ref "IC7") (pin "3") (pinfunction "C_3") (pintype "bidirectional"))
      (node (ref "R24") (pin "1") (pinfunction "1_1") (pintype "passive"))
    )
    (net (code "20") (name "LINE_CR") (class "Default")
      (node (ref "IC2") (pin "31") (pinfunction "(PCINT6/ADC6)PA6_31") (pintype "bidirectional"))
      (node (ref "IC6") (pin "3") (pinfunction "C_3") (pintype "bidirectional"))
      (node (ref "R22") (pin "1") (pinfunction "1_1") (pintype "passive"))
    )
    (net (code "21") (name "LINE_L") (class "Default")
      (node (ref "IC2") (pin "34") (pinfunction "(PCINT3/ADC3)PA3_34") (pintype "bidirectional"))
      (node (ref "IC4") (pin "3") (pinfunction "C_3") (pintype "bidirectional"))
      (node (ref "R18") (pin "1") (pinfunction "1_1") (pintype "passive"))
    )
    (net (code "22") (name "LINE_PWR") (class "Default")
      (node (ref "IC2") (pin "26") (pinfunction "(PCINT23/TOSC2)PC7_26") (pintype "output"))
      (node (ref "Q5") (pin "1") (pinfunction "G_1") (pintype "passive"))
      (node (ref "R26") (pin "1") (pinfunction "1_1") (pintype "passive"))
    )
    (net (code "23") (name "LINE_R") (class "Default")
      (node (ref "IC2") (pin "30") (pinfunction "(PCINT7/ADC7)PA7_30") (pintype "bidirectional"))
      (node (ref "IC5") (pin "3") (pinfunction "C_3") (pintype "bidirectional"))
      (node (ref "R20") (pin "1") (pinfunction "1_1") (pintype "passive"))
    )
    (net (code "24") (name "MISO") (class "Default")
      (node (ref "BUS2") (pin "5") (pinfunction "5_5") (pintype "passive"))
      (node (ref "IC2") (pin "2") (pinfunction "(PCINT14/MISO)PB6_2") (pintype "bidirectional"))
      (node (ref "ISP") (pin "1") (pinfunction "MISO_1") (pintype "input"))
    )
    (net (code "25") (name "MOSI") (class "Default")
      (node (ref "BUS2") (pin "4") (pinfunction "4_4") (pintype "passive"))
      (node (ref "IC2") (pin "1") (pinfunction "(PCINT13/MOSI)PB5_1") (pintype "bidirectional"))
      (node (ref "ISP") (pin "4") (pinfunction "MOSI_4") (pintype "output"))
    )
    (net (code "26") (name "MOTL_PWM") (class "Default")
      (node (ref "IC2") (pin "16") (pinfunction "(PCINT31/OC2A)PD7_16") (pintype "bidirectional"))
      (node (ref "IC8") (pin "12") (pinfunction "I0_12") (pintype "input"))
      (node (ref "IC8") (pin "9") (pinfunction "I0_9") (pintype "input"))
      (node (ref "R28") (pin "2") (pinfunction "2_2") (pintype "passive"))
    )
    (net (code "27") (name "MOTR_PWM") (class "Default")
      (node (ref "IC2") (pin "15") (pinfunction "(PCINT30/OC2B/ICP)PD6_15") (pintype "bidirectional"))
      (node (ref "IC8") (pin "1") (pinfunction "I0_1") (pintype "input"))
      (node (ref "IC8") (pin "4") (pinfunction "I0_4") (pintype "input"))
      (node (ref "R27") (pin "2") (pinfunction "2_2") (pintype "passive"))
    )
    (net (code "28") (name "Net-(IC2-(PCINT29{slash}OC1A)PD5)") (class "Default")
      (node (ref "IC2") (pin "14") (pinfunction "(PCINT29/OC1A)PD5_14") (pintype "bidirectional"))
      (node (ref "Q3") (pin "1") (pinfunction "G_1") (pintype "passive"))
      (node (ref "R13") (pin "2") (pinfunction "2_2") (pintype "passive"))
    )
    (net (code "29") (name "Net-(IC2-AREF)") (class "Default")
      (node (ref "C9") (pin "1") (pinfunction "1_1") (pintype "passive"))
      (node (ref "IC2") (pin "29") (pinfunction "AREF_29") (pintype "passive"))
    )
    (net (code "30") (name "Net-(IC2-XTAL1)") (class "Default")
      (node (ref "C8") (pin "1") (pinfunction "1_1") (pintype "passive"))
      (node (ref "IC2") (pin "8") (pinfunction "XTAL1_8") (pintype "bidirectional"))
      (node (ref "Q2") (pin "P$1") (pinfunction "1_P$1") (pintype "passive"))
    )
    (net (code "31") (name "Net-(IC2-XTAL2)") (class "Default")
      (node (ref "C7") (pin "1") (pinfunction "1_1") (pintype "passive"))
      (node (ref "IC2") (pin "7") (pinfunction "XTAL2_7") (pintype "bidirectional"))
      (node (ref "Q2") (pin "P$3") (pinfunction "2_P$3") (pintype "passive"))
    )
    (net (code "32") (name "Net-(IC3-A)") (class "Default")
      (node (ref "IC3") (pin "1") (pinfunction "A_1") (pintype "bidirectional"))
      (node (ref "R17") (pin "1") (pinfunction "1_1") (pintype "passive"))
    )
    (net (code "33") (name "Net-(IC3-K)") (class "Default")
      (node (ref "IC3") (pin "2") (pinfunction "K_2") (pintype "bidirectional"))
      (node (ref "IC4") (pin "2") (pinfunction "K_2") (pintype "bidirectional"))
      (node (ref "IC5") (pin "2") (pinfunction "K_2") (pintype "bidirectional"))
      (node (ref "IC6") (pin "2") (pinfunction "K_2") (pintype "bidirectional"))
      (node (ref "IC7") (pin "2") (pinfunction "K_2") (pintype "bidirectional"))
      (node (ref "Q5") (pin "3") (pinfunction "D_3") (pintype "passive"))
    )
    (net (code "34") (name "Net-(IC4-A)") (class "Default")
      (node (ref "IC4") (pin "1") (pinfunction "A_1") (pintype "bidirectional"))
      (node (ref "R19") (pin "1") (pinfunction "1_1") (pintype "passive"))
    )
    (net (code "35") (name "Net-(IC5-A)") (class "Default")
      (node (ref "IC5") (pin "1") (pinfunction "A_1") (pintype "bidirectional"))
      (node (ref "R21") (pin "1") (pinfunction "1_1") (pintype "passive"))
    )
    (net (code "36") (name "Net-(IC6-A)") (class "Default")
      (node (ref "IC6") (pin "1") (pinfunction "A_1") (pintype "bidirectional"))
      (node (ref "R23") (pin "1") (pinfunction "1_1") (pintype "passive"))
    )
    (net (code "37") (name "Net-(IC7-A)") (class "Default")
      (node (ref "IC7") (pin "1") (pinfunction "A_1") (pintype "bidirectional"))
      (node (ref "R25") (pin "1") (pinfunction "1_1") (pintype "passive"))
    )
    (net (code "38") (name "Net-(IC8A-O)") (class "Default")
      (node (ref "IC8") (pin "3") (pinfunction "O_3") (pintype "output"))
      (node (ref "U3") (pin "16") (pinfunction "AIN1_16") (pintype "bidirectional"))
    )
    (net (code "39") (name "Net-(IC8B-O)") (class "Default")
      (node (ref "IC8") (pin "6") (pinfunction "O_6") (pintype "output"))
      (node (ref "U3") (pin "15") (pinfunction "AIN2_15") (pintype "bidirectional"))
    )
    (net (code "40") (name "Net-(IC8C-O)") (class "Default")
      (node (ref "IC8") (pin "8") (pinfunction "O_8") (pintype "output"))
      (node (ref "U3") (pin "9") (pinfunction "BIN1_9") (pintype "bidirectional"))
    )
    (net (code "41") (name "Net-(IC8D-O)") (class "Default")
      (node (ref "IC8") (pin "11") (pinfunction "O_11") (pintype "output"))
      (node (ref "U3") (pin "10") (pinfunction "BIN2_10") (pintype "bidirectional"))
    )
    (net (code "42") (name "Net-(IC9-A)") (class "Default")
      (node (ref "IC9") (pin "3") (pinfunction "A_3") (pintype "passive"))
      (node (ref "R31") (pin "1") (pinfunction "1_1") (pintype "passive"))
    )
    (net (code "43") (name "Net-(IC10-A)") (class "Default")
      (node (ref "IC10") (pin "3") (pinfunction "A_3") (pintype "passive"))
      (node (ref "R33") (pin "1") (pinfunction "1_1") (pintype "passive"))
    )
    (net (code "44") (name "Net-(IC10-COL)") (class "Default")
      (node (ref "IC10") (pin "2") (pinfunction "COL_2") (pintype "passive"))
      (node (ref "IC11") (pin "3") (pinfunction "+IN_3") (pintype "input"))
      (node (ref "R34") (pin "1") (pinfunction "1_1") (pintype "passive"))
    )
    (net (code "45") (name "Net-(IC11A--IN)") (class "Default")
      (node (ref "IC11") (pin "2") (pinfunction "-IN_2") (pintype "input"))
      (node (ref "R36") (pin "2") (pinfunction "S_2") (pintype "passive"))
    )
    (net (code "46") (name "Net-(IC11B-+IN)") (class "Default")
      (node (ref "IC11") (pin "5") (pinfunction "+IN_5") (pintype "input"))
      (node (ref "IC9") (pin "2") (pinfunction "COL_2") (pintype "passive"))
      (node (ref "R32") (pin "1") (pinfunction "1_1") (pintype "passive"))
      (node (ref "TP3") (pin "TP") (pinfunction "TP_TP") (pintype "input"))
    )
    (net (code "47") (name "Net-(IC11B--IN)") (class "Default")
      (node (ref "IC11") (pin "6") (pinfunction "-IN_6") (pintype "input"))
      (node (ref "R35") (pin "2") (pinfunction "S_2") (pintype "passive"))
    )
    (net (code "48") (name "Net-(IC12-GND)") (class "Default")
      (node (ref "IC12") (pin "1") (pinfunction "GND_1") (pintype "power_in"))
      (node (ref "R37") (pin "1") (pinfunction "1_1") (pintype "passive"))
      (node (ref "R38") (pin "1") (pinfunction "E_1") (pintype "passive"))
      (node (ref "R38") (pin "2") (pinfunction "S_2") (pintype "passive"))
    )
    (net (code "49") (name "Net-(LED1-PadA)") (class "Default")
      (node (ref "LED1") (pin "A") (pinfunction "A_A") (pintype "passive"))
      (node (ref "R1") (pin "1") (pinfunction "1_1") (pintype "passive"))
    )
    (net (code "50") (name "Net-(LED1-PadC)") (class "Default")
      (node (ref "LED1") (pin "C") (pinfunction "C_C") (pintype "passive"))
      (node (ref "LED3") (pin "A") (pinfunction "A_A") (pintype "passive"))
    )
    (net (code "51") (name "Net-(LED2-PadA)") (class "Default")
      (node (ref "LED2") (pin "A") (pinfunction "A_A") (pintype "passive"))
      (node (ref "R2") (pin "1") (pinfunction "1_1") (pintype "passive"))
    )
    (net (code "52") (name "Net-(LED2-PadC)") (class "Default")
      (node (ref "LED2") (pin "C") (pinfunction "C_C") (pintype "passive"))
      (node (ref "LED4") (pin "A") (pinfunction "A_A") (pintype "passive"))
    )
    (net (code "53") (name "Net-(LED5A-C)") (class "Default")
      (node (ref "LED5") (pin "1") (pinfunction "C_1") (pintype "passive"))
      (node (ref "R8") (pin "2") (pinfunction "2_2") (pintype "passive"))
    )
    (net (code "54") (name "Net-(LED5B-C)") (class "Default")
      (node (ref "LED5") (pin "3") (pinfunction "C_3") (pintype "passive"))
      (node (ref "R9") (pin "2") (pinfunction "2_2") (pintype "passive"))
    )
    (net (code "55") (name "Net-(MOT_FLT-PadA)") (class "Default")
      (node (ref "MOT_FLT") (pin "A") (pinfunction "A_A") (pintype "passive"))
      (node (ref "R29") (pin "2") (pinfunction "2_2") (pintype "passive"))
    )
    (net (code "56") (name "Net-(PWR-PadA)") (class "Default")
      (node (ref "PWR") (pin "A") (pinfunction "A_A") (pintype "passive"))
      (node (ref "R4") (pin "1") (pinfunction "1_1") (pintype "passive"))
    )
    (net (code "57") (name "Net-(Q1-D)") (class "Default")
      (node (ref "LED3") (pin "C") (pinfunction "C_C") (pintype "passive"))
      (node (ref "LED4") (pin "C") (pinfunction "C_C") (pintype "passive"))
      (node (ref "Q1") (pin "3") (pinfunction "D_3") (pintype "passive"))
    )
    (net (code "58") (name "Net-(Q3-D)") (class "Default")
      (node (ref "Q3") (pin "3") (pinfunction "D_3") (pintype "passive"))
      (node (ref "SP1") (pin "-") (pinfunction "2_-") (pintype "passive"))
    )
    (net (code "59") (name "Net-(Q6-PadS)") (class "Default")
      (node (ref "Q6") (pin "S") (pinfunction "S_S") (pintype "passive"))
      (node (ref "R31") (pin "2") (pinfunction "2_2") (pintype "passive"))
      (node (ref "R32") (pin "2") (pinfunction "2_2") (pintype "passive"))
      (node (ref "R33") (pin "2") (pinfunction "2_2") (pintype "passive"))
      (node (ref "R34") (pin "2") (pinfunction "2_2") (pintype "passive"))
    )
    (net (code "60") (name "Net-(R15-Pad1)") (class "Default")
      (node (ref "R15") (pin "1") (pinfunction "1_1") (pintype "passive"))
      (node (ref "SJ2") (pin "1") (pinfunction "1_1") (pintype "passive"))
    )
    (net (code "61") (name "Net-(S1-P)") (class "Default")
      (node (ref "JP1") (pin "1") (pinfunction "1_1") (pintype "passive"))
      (node (ref "S1") (pin "2") (pinfunction "P_2") (pintype "passive"))
      (node (ref "X2") (pin "1") (pinfunction "S_1") (pintype "passive"))
    )
    (net (code "62") (name "Net-(U1-VCC)") (class "Default")
      (node (ref "Q4") (pin "S") (pinfunction "S_S") (pintype "passive"))
      (node (ref "U1") (pin "2") (pinfunction "VCC_2") (pintype "bidirectional"))
    )
    (net (code "63") (name "Net-(U3-AOUT1)") (class "Default")
      (node (ref "U2") (pin "R_MOTOR_A") (pinfunction "R_MOTOR_A_R_MOTOR_A") (pintype "bidirectional"))
      (node (ref "U3") (pin "2") (pinfunction "AOUT1_2") (pintype "bidirectional"))
    )
    (net (code "64") (name "Net-(U3-AOUT2)") (class "Default")
      (node (ref "U2") (pin "R_MOTOR_B") (pinfunction "R_MOTOR_B_R_MOTOR_B") (pintype "bidirectional"))
      (node (ref "U3") (pin "4") (pinfunction "AOUT2_4") (pintype "bidirectional"))
    )
    (net (code "65") (name "Net-(U3-BOUT1)") (class "Default")
      (node (ref "U2") (pin "L_MOTOR_B") (pinfunction "L_MOTOR_B_L_MOTOR_B") (pintype "bidirectional"))
      (node (ref "U3") (pin "7") (pinfunction "BOUT1_7") (pintype "bidirectional"))
    )
    (net (code "66") (name "Net-(U3-BOUT2)") (class "Default")
      (node (ref "U2") (pin "L_MOTOR_A") (pinfunction "L_MOTOR_A_L_MOTOR_A") (pintype "bidirectional"))
      (node (ref "U3") (pin "5") (pinfunction "BOUT2_5") (pintype "bidirectional"))
    )
    (net (code "67") (name "Net-(U3-NFAULT)") (class "Default")
      (node (ref "MOT_FLT") (pin "C") (pinfunction "C_C") (pintype "passive"))
      (node (ref "U3") (pin "8") (pinfunction "NFAULT_8") (pintype "bidirectional"))
    )
    (net (code "68") (name "Net-(U3-VCP)") (class "Default")
      (node (ref "C15") (pin "2") (pinfunction "2_2") (pintype "passive"))
      (node (ref "U3") (pin "11") (pinfunction "VCP_11") (pintype "bidirectional"))
    )
    (net (code "69") (name "Net-(U3-VINT)") (class "Default")
      (node (ref "C16") (pin "1") (pinfunction "1_1") (pintype "passive"))
      (node (ref "U3") (pin "14") (pinfunction "VINT_14") (pintype "bidirectional"))
    )
    (net (code "70") (name "Net-(X1A-S)") (class "Default")
      (node (ref "X1") (pin "1") (pinfunction "S_1") (pintype "passive"))
      (node (ref "X2") (pin "2") (pinfunction "S_2") (pintype "passive"))
    )
    (net (code "71") (name "RESET") (class "Default")
      (node (ref "BUS2") (pin "2") (pinfunction "2_2") (pintype "passive"))
      (node (ref "C6") (pin "1") (pinfunction "1_1") (pintype "passive"))
      (node (ref "IC2") (pin "4") (pinfunction "RESET_4") (pintype "input"))
      (node (ref "ISP") (pin "5") (pinfunction "RST_5") (pintype "output"))
      (node (ref "R7") (pin "1") (pinfunction "1_1") (pintype "passive"))
      (node (ref "SW3") (pin "1") (pinfunction "1_1") (pintype "bidirectional"))
      (node (ref "U3") (pin "1") (pinfunction "NSLEEP_1") (pintype "bidirectional"))
    )
    (net (code "72") (name "RXD") (class "Default")
      (node (ref "BUS2") (pin "6") (pinfunction "6_6") (pintype "passive"))
      (node (ref "IC2") (pin "9") (pinfunction "(PCINT24/RXD0)PD0_9") (pintype "bidirectional"))
      (node (ref "U1") (pin "4") (pinfunction "TXD_4") (pintype "bidirectional"))
    )
    (net (code "73") (name "SCK") (class "Default")
      (node (ref "BUS2") (pin "3") (pinfunction "3_3") (pintype "passive"))
      (node (ref "IC2") (pin "3") (pinfunction "(PCINT15/SCK)PB7_3") (pintype "bidirectional"))
      (node (ref "ISP") (pin "3") (pinfunction "SCK_3") (pintype "output"))
    )
    (net (code "74") (name "SCL") (class "Default")
      (node (ref "BUS1") (pin "4") (pinfunction "4_4") (pintype "passive"))
      (node (ref "IC2") (pin "19") (pinfunction "(PCINT16/SCL)PC0_19") (pintype "output"))
      (node (ref "R11") (pin "1") (pinfunction "1_1") (pintype "passive"))
    )
    (net (code "75") (name "SDA") (class "Default")
      (node (ref "BUS1") (pin "5") (pinfunction "5_5") (pintype "passive"))
      (node (ref "IC2") (pin "20") (pinfunction "(PCINT17/SDA)PC1_20") (pintype "output"))
      (node (ref "R10") (pin "1") (pinfunction "1_1") (pintype "passive"))
    )
    (net (code "76") (name "START") (class "Default")
      (node (ref "BUS1") (pin "3") (pinfunction "3_3") (pintype "passive"))
      (node (ref "IC2") (pin "44") (pinfunction "(PCINT12/OC0B/~{SS})PB4_44") (pintype "bidirectional"))
      (node (ref "SW1") (pin "4") (pinfunction "4_4") (pintype "bidirectional"))
    )
    (net (code "77") (name "TXD") (class "Default")
      (node (ref "BUS2") (pin "7") (pinfunction "7_7") (pintype "passive"))
      (node (ref "IC2") (pin "10") (pinfunction "(PCINT25/TXD0)PD1_10") (pintype "bidirectional"))
      (node (ref "R14") (pin "2") (pinfunction "2_2") (pintype "passive"))
    )
    (net (code "78") (name "TXD_3V3") (class "Default")
      (node (ref "R14") (pin "1") (pinfunction "1_1") (pintype "passive"))
      (node (ref "R15") (pin "2") (pinfunction "2_2") (pintype "passive"))
      (node (ref "U1") (pin "5") (pinfunction "RXD_5") (pintype "bidirectional"))
    )
    (net (code "79") (name "USER") (class "Default")
      (node (ref "IC2") (pin "43") (pinfunction "(PCINT11/OC0A/AIN1)PB3_43") (pintype "bidirectional"))
      (node (ref "SW2") (pin "4") (pinfunction "4_4") (pintype "bidirectional"))
    )
    (net (code "80") (name "V+") (class "Default")
      (node (ref "BUS1") (pin "2") (pinfunction "2_2") (pintype "passive"))
      (node (ref "C1") (pin "+") (pinfunction "+_+") (pintype "passive"))
      (node (ref "C2") (pin "1") (pinfunction "1_1") (pintype "passive"))
      (node (ref "C20") (pin "1") (pinfunction "1_1") (pintype "passive"))
      (node (ref "IC1") (pin "3") (pinfunction "VIN_3") (pintype "input"))
      (node (ref "IC12") (pin "3") (pinfunction "VIN_3") (pintype "input"))
      (node (ref "R1") (pin "2") (pinfunction "2_2") (pintype "passive"))
      (node (ref "R2") (pin "2") (pinfunction "2_2") (pintype "passive"))
      (node (ref "R3") (pin "2") (pinfunction "2_2") (pintype "passive"))
      (node (ref "S1") (pin "3") (pinfunction "S_3") (pintype "passive"))
    )
    (net (code "81") (name "VBAT") (class "Default")
      (node (ref "IC2") (pin "35") (pinfunction "(PCINT2/ADC2)PA2_35") (pintype "bidirectional"))
      (node (ref "R3") (pin "1") (pinfunction "1_1") (pintype "passive"))
      (node (ref "R5") (pin "2") (pinfunction "2_2") (pintype "passive"))
    )
    (net (code "82") (name "VPP") (class "Default")
      (node (ref "C13") (pin "1") (pinfunction "1_1") (pintype "passive"))
      (node (ref "C14") (pin "1") (pinfunction "1_1") (pintype "passive"))
      (node (ref "C15") (pin "1") (pinfunction "1_1") (pintype "passive"))
      (node (ref "C19") (pin "+") (pinfunction "+_+") (pintype "passive"))
      (node (ref "IC12") (pin "2") (pinfunction "VOUT_2") (pintype "output"))
      (node (ref "R29") (pin "1") (pinfunction "1_1") (pintype "passive"))
      (node (ref "R37") (pin "2") (pinfunction "2_2") (pintype "passive"))
      (node (ref "U3") (pin "12") (pinfunction "VM_12") (pintype "bidirectional"))
    )
    (net (code "83") (name "unconnected-(S1-O-Pad1)") (class "Default")
      (node (ref "S1") (pin "1") (pinfunction "O_1") (pintype "passive"))
    )
    (net (code "84") (name "unconnected-(SW1-Pad2)") (class "Default")
      (node (ref "SW1") (pin "2") (pinfunction "2_2") (pintype "bidirectional"))
    )
    (net (code "85") (name "unconnected-(SW1-Pad3)") (class "Default")
      (node (ref "SW1") (pin "3") (pinfunction "3_3") (pintype "bidirectional"))
    )
    (net (code "86") (name "unconnected-(SW1-Pad5)") (class "Default")
      (node (ref "SW1") (pin "5") (pinfunction "5_5") (pintype "bidirectional"))
    )
    (net (code "87") (name "unconnected-(SW2-Pad2)") (class "Default")
      (node (ref "SW2") (pin "2") (pinfunction "2_2") (pintype "bidirectional"))
    )
    (net (code "88") (name "unconnected-(SW2-Pad3)") (class "Default")
      (node (ref "SW2") (pin "3") (pinfunction "3_3") (pintype "bidirectional"))
    )
    (net (code "89") (name "unconnected-(SW2-Pad5)") (class "Default")
      (node (ref "SW2") (pin "5") (pinfunction "5_5") (pintype "bidirectional"))
    )
    (net (code "90") (name "unconnected-(SW3-Pad2)") (class "Default")
      (node (ref "SW3") (pin "2") (pinfunction "2_2") (pintype "bidirectional"))
    )
    (net (code "91") (name "unconnected-(SW3-Pad3)") (class "Default")
      (node (ref "SW3") (pin "3") (pinfunction "3_3") (pintype "bidirectional"))
    )
    (net (code "92") (name "unconnected-(SW3-Pad5)") (class "Default")
      (node (ref "SW3") (pin "5") (pinfunction "5_5") (pintype "bidirectional"))
    )
    (net (code "93") (name "unconnected-(U1-EN-Pad1)") (class "Default")
      (node (ref "U1") (pin "1") (pinfunction "EN_1") (pintype "bidirectional"))
    )
    (net (code "94") (name "unconnected-(U1-STATE-Pad6)") (class "Default")
      (node (ref "U1") (pin "6") (pinfunction "STATE_6") (pintype "bidirectional"))
    )
  )
)
